# DefenderV1.net
KiCad netlist of a schematic drawn in EAGLE
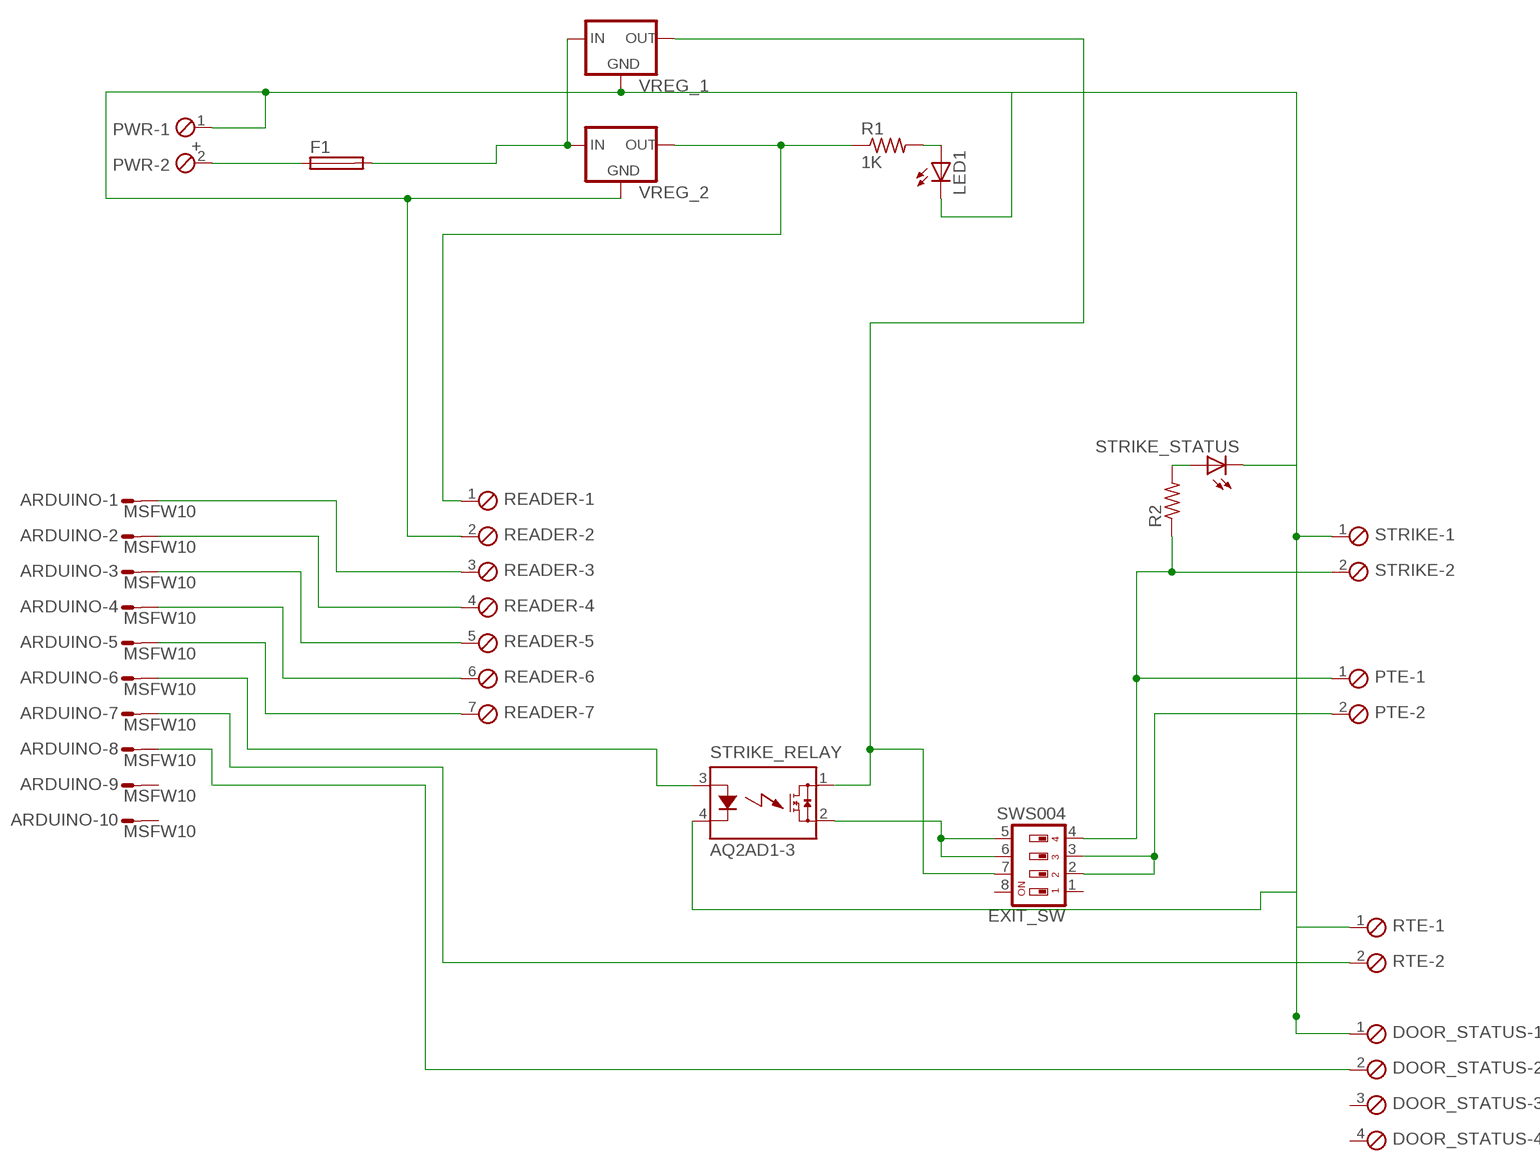
[diagram p0: schematic, sheet 1]

(export (version "E")
  (design (tool "Eeschema 10.0.6"))
  (components
    (comp (ref "ARDUINO")
      (value "MSFW10")
      (footprint "eagle-import:MSFW10")
      (libsource (lib "eagle-import") (part "MSFW10"))
    )
    (comp (ref "DOOR_STATUS")
      (value "MPT4")
      (footprint "eagle-import:4POL254")
      (libsource (lib "eagle-import") (part "MPT4"))
    )
    (comp (ref "EXIT_SW")
      (value "SWS004")
      (footprint "eagle-import:SMS-004")
      (libsource (lib "eagle-import") (part "SWS004"))
    )
    (comp (ref "F1")
      (value "GSH15")
      (footprint "eagle-import:GSH15")
      (fields (field (name "MPN") "64900001039"))
      (libsource (lib "eagle-import") (part "GSH15"))
    )
    (comp (ref "LED1")
      (value "LED5MM")
      (footprint "eagle-import:LED5MM")
      (libsource (lib "eagle-import") (part "LED5MM"))
    )
    (comp (ref "PTE")
      (value "MPT2")
      (footprint "eagle-import:2POL254")
      (libsource (lib "eagle-import") (part "MPT2"))
    )
    (comp (ref "PWR")
      (value "+")
      (footprint "eagle-import:2POL254")
      (libsource (lib "eagle-import") (part "MPT2"))
    )
    (comp (ref "R1")
      (value "1K")
      (footprint "eagle-import:0204_7")
      (libsource (lib "eagle-import") (part "R-US_0204/7"))
    )
    (comp (ref "R2")
      (value "R-US_0204/7")
      (footprint "eagle-import:0204_7")
      (libsource (lib "eagle-import") (part "R-US_0204/7"))
    )
    (comp (ref "READER")
      (value "MPT7")
      (footprint "eagle-import:7POL254")
      (libsource (lib "eagle-import") (part "MPT7"))
    )
    (comp (ref "RTE")
      (value "MPT2")
      (footprint "eagle-import:2POL254")
      (libsource (lib "eagle-import") (part "MPT2"))
    )
    (comp (ref "STRIKE")
      (value "MPT2")
      (footprint "eagle-import:2POL254")
      (libsource (lib "eagle-import") (part "MPT2"))
    )
    (comp (ref "STRIKE_RELAY")
      (value "AQ2AD1-3")
      (footprint "eagle-import:AQ1")
      (fields (field (name "MPN") "AQ2AD1-3/28VDC"))
      (libsource (lib "eagle-import") (part "AQ2AD1-3"))
    )
    (comp (ref "STRIKE_STATUS")
      (value "LED5MM")
      (footprint "eagle-import:LED5MM")
      (libsource (lib "eagle-import") (part "LED5MM"))
    )
    (comp (ref "VREG_1")
      (value "78XXL")
      (footprint "eagle-import:78XXL")
      (libsource (lib "eagle-import") (part "78XXL"))
    )
    (comp (ref "VREG_2")
      (value "78XXL")
      (footprint "eagle-import:78XXL")
      (libsource (lib "eagle-import") (part "78XXL"))
    )
  )
  (nets
    (net (code "1") (name "Net-(ARDUINOA-S)") (class "Default")
      (node (ref "ARDUINO") (pin "1") (pinfunction "S_1") (pintype "passive"))
      (node (ref "READER") (pin "3") (pinfunction "1_3") (pintype "passive"))
    )
    (net (code "2") (name "Net-(ARDUINOC-S)") (class "Default")
      (node (ref "ARDUINO") (pin "2") (pinfunction "S_2") (pintype "passive"))
      (node (ref "READER") (pin "4") (pinfunction "1_4") (pintype "passive"))
    )
    (net (code "3") (name "Net-(ARDUINOD-S)") (class "Default")
      (node (ref "ARDUINO") (pin "3") (pinfunction "S_3") (pintype "passive"))
      (node (ref "READER") (pin "5") (pinfunction "1_5") (pintype "passive"))
    )
    (net (code "4") (name "Net-(ARDUINOE-S)") (class "Default")
      (node (ref "ARDUINO") (pin "4") (pinfunction "S_4") (pintype "passive"))
      (node (ref "READER") (pin "6") (pinfunction "1_6") (pintype "passive"))
    )
    (net (code "5") (name "Net-(ARDUINOF-S)") (class "Default")
      (node (ref "ARDUINO") (pin "5") (pinfunction "S_5") (pintype "passive"))
      (node (ref "READER") (pin "7") (pinfunction "1_7") (pintype "passive"))
    )
    (net (code "6") (name "Net-(ARDUINOG-S)") (class "Default")
      (node (ref "ARDUINO") (pin "6") (pinfunction "S_6") (pintype "passive"))
      (node (ref "STRIKE_RELAY") (pin "3") (pinfunction "A_3") (pintype "passive"))
    )
    (net (code "7") (name "Net-(ARDUINOH-S)") (class "Default")
      (node (ref "ARDUINO") (pin "7") (pinfunction "S_7") (pintype "passive"))
      (node (ref "RTE") (pin "2") (pinfunction "1_2") (pintype "passive"))
    )
    (net (code "8") (name "Net-(ARDUINOI-S)") (class "Default")
      (node (ref "ARDUINO") (pin "8") (pinfunction "S_8") (pintype "passive"))
      (node (ref "DOOR_STATUS") (pin "2") (pinfunction "1_2") (pintype "passive"))
    )
    (net (code "9") (name "Net-(F1-Pad2)") (class "Default")
      (node (ref "F1") (pin "2") (pinfunction "2_2") (pintype "passive"))
      (node (ref "VREG_1") (pin "IN") (pinfunction "IN_IN") (pintype "input"))
      (node (ref "VREG_2") (pin "IN") (pinfunction "IN_IN") (pintype "input"))
    )
    (net (code "10") (name "Net-(LED1-C)") (class "Default")
      (node (ref "DOOR_STATUS") (pin "1") (pinfunction "1_1") (pintype "passive"))
      (node (ref "LED1") (pin "K") (pinfunction "C_K") (pintype "passive"))
      (node (ref "PWR") (pin "1") (pinfunction "1_1") (pintype "passive"))
      (node (ref "READER") (pin "2") (pinfunction "1_2") (pintype "passive"))
      (node (ref "RTE") (pin "1") (pinfunction "1_1") (pintype "passive"))
      (node (ref "STRIKE") (pin "1") (pinfunction "1_1") (pintype "passive"))
      (node (ref "STRIKE_RELAY") (pin "4") (pinfunction "K_4") (pintype "passive"))
      (node (ref "STRIKE_STATUS") (pin "K") (pinfunction "C_K") (pintype "passive"))
      (node (ref "VREG_1") (pin "GND") (pinfunction "GND_GND") (pintype "input"))
      (node (ref "VREG_2") (pin "GND") (pinfunction "GND_GND") (pintype "input"))
    )
    (net (code "11") (name "Net-(LED1-PadA)") (class "Default")
      (node (ref "LED1") (pin "A") (pinfunction "A_A") (pintype "passive"))
      (node (ref "R1") (pin "2") (pinfunction "2_2") (pintype "passive"))
    )
    (net (code "12") (name "Net-(PTEB-1)") (class "Default")
      (node (ref "EXIT_SW") (pin "2") (pinfunction "2_2") (pintype "passive"))
      (node (ref "EXIT_SW") (pin "3") (pinfunction "3_3") (pintype "passive"))
      (node (ref "PTE") (pin "2") (pinfunction "1_2") (pintype "passive"))
    )
    (net (code "13") (name "Net-(PWRB-1)") (class "Default")
      (node (ref "F1") (pin "1") (pinfunction "1_1") (pintype "passive"))
      (node (ref "PWR") (pin "2") (pinfunction "1_2") (pintype "passive"))
    )
    (net (code "14") (name "Net-(R1-Pad1)") (class "Default")
      (node (ref "R1") (pin "1") (pinfunction "1_1") (pintype "passive"))
      (node (ref "READER") (pin "1") (pinfunction "1_1") (pintype "passive"))
      (node (ref "VREG_2") (pin "OUT") (pinfunction "OUT_OUT") (pintype "passive"))
    )
    (net (code "15") (name "Net-(R2-Pad2)") (class "Default")
      (node (ref "R2") (pin "2") (pinfunction "2_2") (pintype "passive"))
      (node (ref "STRIKE_STATUS") (pin "A") (pinfunction "A_A") (pintype "passive"))
    )
    (net (code "16") (name "Net-(STRIKEB-1)") (class "Default")
      (node (ref "EXIT_SW") (pin "4") (pinfunction "4_4") (pintype "passive"))
      (node (ref "PTE") (pin "1") (pinfunction "1_1") (pintype "passive"))
      (node (ref "R2") (pin "1") (pinfunction "1_1") (pintype "passive"))
      (node (ref "STRIKE") (pin "2") (pinfunction "1_2") (pintype "passive"))
    )
    (net (code "17") (name "Net-(STRIKE_RELAY-DS1)") (class "Default")
      (node (ref "EXIT_SW") (pin "7") (pinfunction "7_7") (pintype "passive"))
      (node (ref "STRIKE_RELAY") (pin "1") (pinfunction "DS1_1") (pintype "passive"))
      (node (ref "VREG_1") (pin "OUT") (pinfunction "OUT_OUT") (pintype "passive"))
    )
    (net (code "18") (name "Net-(STRIKE_RELAY-DS2)") (class "Default")
      (node (ref "EXIT_SW") (pin "5") (pinfunction "5_5") (pintype "passive"))
      (node (ref "EXIT_SW") (pin "6") (pinfunction "6_6") (pintype "passive"))
      (node (ref "STRIKE_RELAY") (pin "2") (pinfunction "DS2_2") (pintype "passive"))
    )
    (net (code "19") (name "unconnected-(ARDUINOB-S-Pad10)") (class "Default")
      (node (ref "ARDUINO") (pin "10") (pinfunction "S_10") (pintype "passive"))
    )
    (net (code "20") (name "unconnected-(ARDUINOJ-S-Pad9)") (class "Default")
      (node (ref "ARDUINO") (pin "9") (pinfunction "S_9") (pintype "passive"))
    )
    (net (code "21") (name "unconnected-(DOOR_STATUSC-1-Pad3)") (class "Default")
      (node (ref "DOOR_STATUS") (pin "3") (pinfunction "1_3") (pintype "passive"))
    )
    (net (code "22") (name "unconnected-(DOOR_STATUSD-1-Pad4)") (class "Default")
      (node (ref "DOOR_STATUS") (pin "4") (pinfunction "1_4") (pintype "passive"))
    )
    (net (code "23") (name "unconnected-(EXIT_SW-Pad1)") (class "Default")
      (node (ref "EXIT_SW") (pin "1") (pinfunction "1_1") (pintype "passive"))
    )
    (net (code "24") (name "unconnected-(EXIT_SW-Pad8)") (class "Default")
      (node (ref "EXIT_SW") (pin "8") (pinfunction "8_8") (pintype "passive"))
    )
  )
)
